# dual_encoder_i2c_revE.net
KiCad netlist of a schematic drawn in EAGLE
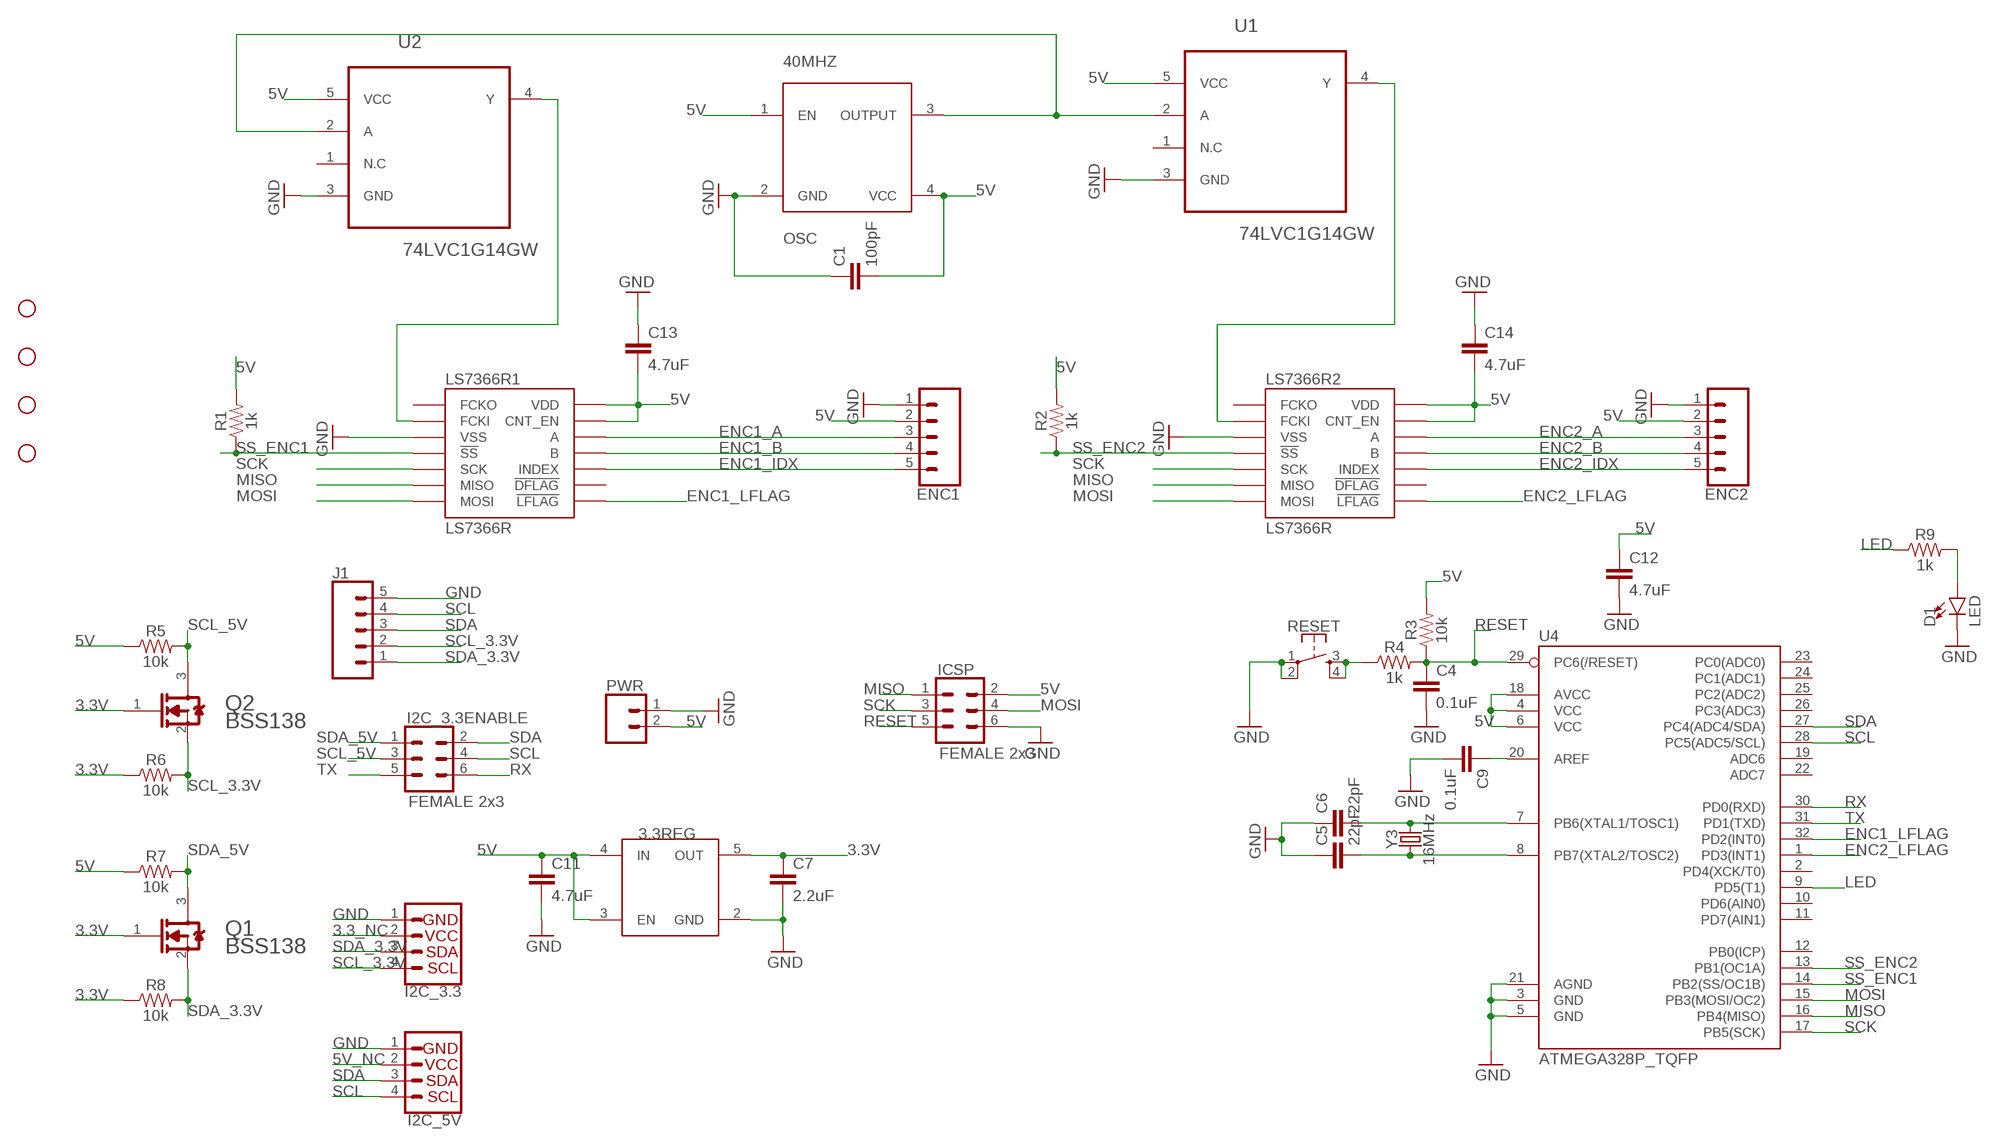
[diagram p0: schematic, sheet 1]

(export (version "E")
  (design (tool "Eeschema 10.0.6"))
  (components
    (comp (ref "3.3REG")
      (value "MIC3490-3.3YM5-TR")
      (footprint "eagle-import:SOT95P285X145-5N")
      (libsource (lib "eagle-import") (part "MIC3490-3.3YM5-TR"))
    )
    (comp (ref "40MHZ")
      (value "OSC")
      (footprint "eagle-import:CB3OSCILLATOR")
      (libsource (lib "eagle-import") (part "OSC"))
    )
    (comp (ref "C1")
      (value "100pF")
      (footprint "eagle-import:0603")
      (libsource (lib "eagle-import") (part "100PF-0603-50V-5%"))
    )
    (comp (ref "C4")
      (value "0.1uF")
      (footprint "eagle-import:0603")
      (libsource (lib "eagle-import") (part "0.1UF-0603-25V-5%"))
    )
    (comp (ref "C5")
      (value "22pF")
      (footprint "eagle-import:0603")
      (libsource (lib "eagle-import") (part "22PF-0603-50V-5%"))
    )
    (comp (ref "C6")
      (value "22pF")
      (footprint "eagle-import:0603")
      (libsource (lib "eagle-import") (part "22PF-0603-50V-5%"))
    )
    (comp (ref "C7")
      (value "2.2uF")
      (footprint "eagle-import:0603")
      (libsource (lib "eagle-import") (part "2.2UF-0603-10V-20%"))
    )
    (comp (ref "C9")
      (value "0.1uF")
      (footprint "eagle-import:0603")
      (libsource (lib "eagle-import") (part "0.1UF-0603-25V-5%"))
    )
    (comp (ref "C11")
      (value "4.7uF")
      (footprint "eagle-import:1206")
      (libsource (lib "eagle-import") (part "4.7UF-1206-16V-(+80/-20%)"))
    )
    (comp (ref "C12")
      (value "4.7uF")
      (footprint "eagle-import:1206")
      (libsource (lib "eagle-import") (part "4.7UF-1206-16V-(+80/-20%)"))
    )
    (comp (ref "C13")
      (value "4.7uF")
      (footprint "eagle-import:1206")
      (libsource (lib "eagle-import") (part "4.7UF-1206-16V-(+80/-20%)"))
    )
    (comp (ref "C14")
      (value "4.7uF")
      (footprint "eagle-import:1206")
      (libsource (lib "eagle-import") (part "4.7UF-1206-16V-(+80/-20%)"))
    )
    (comp (ref "D1")
      (value "LED")
      (footprint "eagle-import:LED-0603")
      (libsource (lib "eagle-import") (part "LED0603"))
    )
    (comp (ref "ENC1")
      (value "CONN_05")
      (footprint "eagle-import:1X05")
      (libsource (lib "eagle-import") (part "CONN_05"))
    )
    (comp (ref "ENC2")
      (value "CONN_05")
      (footprint "eagle-import:1X05")
      (libsource (lib "eagle-import") (part "CONN_05"))
    )
    (comp (ref "H1")
      (value "STAND-OFF")
      (footprint "eagle-import:STAND-OFF")
      (libsource (lib "eagle-import") (part "STAND-OFF"))
    )
    (comp (ref "H2")
      (value "STAND-OFF")
      (footprint "eagle-import:STAND-OFF")
      (libsource (lib "eagle-import") (part "STAND-OFF"))
    )
    (comp (ref "H3")
      (value "STAND-OFF")
      (footprint "eagle-import:STAND-OFF")
      (libsource (lib "eagle-import") (part "STAND-OFF"))
    )
    (comp (ref "H4")
      (value "STAND-OFF")
      (footprint "eagle-import:STAND-OFF")
      (libsource (lib "eagle-import") (part "STAND-OFF"))
    )
    (comp (ref "I2C_3.3")
      (value "QWIIC_CONNECTORJS-1MM")
      (footprint "eagle-import:JST04_1MM_RA")
      (libsource (lib "eagle-import") (part "QWIIC_CONNECTORJS-1MM"))
    )
    (comp (ref "I2C_3.3ENABLE")
      (value "FEMALE 2x3")
      (footprint "eagle-import:2X3")
      (libsource (lib "eagle-import") (part "CONN_03X2FEMALE"))
    )
    (comp (ref "I2C_5V")
      (value "QWIIC_CONNECTORJS-1MM")
      (footprint "eagle-import:JST04_1MM_RA")
      (libsource (lib "eagle-import") (part "QWIIC_CONNECTORJS-1MM"))
    )
    (comp (ref "ICSP")
      (value "FEMALE 2x3")
      (footprint "eagle-import:2X3")
      (libsource (lib "eagle-import") (part "CONN_03X2FEMALE"))
    )
    (comp (ref "J1")
      (value "CONN_05")
      (footprint "eagle-import:1X05")
      (libsource (lib "eagle-import") (part "CONN_05"))
    )
    (comp (ref "LS7366R1")
      (value "LS7366R")
      (footprint "eagle-import:SOIC14")
      (fields (field (name "MF") "LSI"))
      (libsource (lib "eagle-import") (part "LS7366R"))
    )
    (comp (ref "LS7366R2")
      (value "LS7366R")
      (footprint "eagle-import:SOIC14")
      (fields (field (name "MF") "LSI"))
      (libsource (lib "eagle-import") (part "LS7366R"))
    )
    (comp (ref "PWR")
      (value "CONN_02-JST-2MM-SMT")
      (footprint "eagle-import:JST-2-SMD")
      (libsource (lib "eagle-import") (part "CONN_02-JST-2MM-SMT"))
    )
    (comp (ref "Q1")
      (value "ON_SEMI_BSS138ON_SEMI_BSS138_0_0")
      (footprint "eagle-import:ON_SEMI_BSS138_0")
      (fields
        (field (name "DIGIKEY_PART_NUMBER") "BSS138CT-ND")
        (field (name "MF") "ON Semi")
        (field (name "MOUSER_PART_NUMBER") "512-BSS138")
      )
      (libsource (lib "eagle-import") (part "ON_SEMI_BSS138ON_SEMI_BSS138_0_0"))
    )
    (comp (ref "Q2")
      (value "ON_SEMI_BSS138ON_SEMI_BSS138_0_0")
      (footprint "eagle-import:ON_SEMI_BSS138_0")
      (fields
        (field (name "DIGIKEY_PART_NUMBER") "BSS138CT-ND")
        (field (name "MF") "ON Semi")
        (field (name "MOUSER_PART_NUMBER") "512-BSS138")
      )
      (libsource (lib "eagle-import") (part "ON_SEMI_BSS138ON_SEMI_BSS138_0_0"))
    )
    (comp (ref "R1")
      (value "1k")
      (footprint "eagle-import:0603")
      (libsource (lib "eagle-import") (part "1KOHM-0603-1/10W-1%"))
    )
    (comp (ref "R2")
      (value "1k")
      (footprint "eagle-import:0603")
      (libsource (lib "eagle-import") (part "1KOHM-0603-1/10W-1%"))
    )
    (comp (ref "R3")
      (value "10k")
      (footprint "eagle-import:0603")
      (libsource (lib "eagle-import") (part "10KOHM-0603-1/10W-1%"))
    )
    (comp (ref "R4")
      (value "1k")
      (footprint "eagle-import:0603")
      (libsource (lib "eagle-import") (part "1KOHM-0603-1/10W-1%"))
    )
    (comp (ref "R5")
      (value "10k")
      (footprint "eagle-import:0603")
      (libsource (lib "eagle-import") (part "10KOHM-0603-1/10W-1%"))
    )
    (comp (ref "R6")
      (value "10k")
      (footprint "eagle-import:0603")
      (libsource (lib "eagle-import") (part "10KOHM-0603-1/10W-1%"))
    )
    (comp (ref "R7")
      (value "10k")
      (footprint "eagle-import:0603")
      (libsource (lib "eagle-import") (part "10KOHM-0603-1/10W-1%"))
    )
    (comp (ref "R8")
      (value "10k")
      (footprint "eagle-import:0603")
      (libsource (lib "eagle-import") (part "10KOHM-0603-1/10W-1%"))
    )
    (comp (ref "R9")
      (value "1k")
      (footprint "eagle-import:0603")
      (libsource (lib "eagle-import") (part "1KOHM-0603-1/10W-1%"))
    )
    (comp (ref "RESET")
      (value "MOMENTARY-SWITCH-SPST-2-SMD-5.2MM")
      (footprint "eagle-import:TACTILE_SWITCH_SMD_5.2MM")
      (libsource (lib "eagle-import") (part "MOMENTARY-SWITCH-SPST-2-SMD-5.2MM"))
    )
    (comp (ref "U1")
      (value "74LVC1G14GW")
      (footprint "eagle-import:SOT65P210X110-5N")
      (fields (field (name "MF") "NXP Semiconductors"))
      (libsource (lib "eagle-import") (part "74LVC1G14GW"))
    )
    (comp (ref "U2")
      (value "74LVC1G14GW")
      (footprint "eagle-import:SOT65P210X110-5N")
      (fields (field (name "MF") "NXP Semiconductors"))
      (libsource (lib "eagle-import") (part "74LVC1G14GW"))
    )
    (comp (ref "U4")
      (value "ATMEGA328P_TQFP")
      (footprint "eagle-import:TQFP32-08")
      (libsource (lib "eagle-import") (part "ATMEGA328P_TQFP"))
    )
    (comp (ref "Y3")
      (value "16MHz")
      (footprint "eagle-import:CRYSTAL-SMD-5X3.2-4PAD")
      (libsource (lib "eagle-import") (part "CRYSTAL-16MHZSMD-5X3.2"))
    )
  )
  (nets
    (net (code "1") (name "/3.3V") (class "Default")
      (node (ref "3.3REG") (pin "5") (pinfunction "OUT_5") (pintype "output"))
      (node (ref "C7") (pin "1") (pinfunction "1_1") (pintype "passive"))
      (node (ref "Q1") (pin "1") (pinfunction "G_1") (pintype "bidirectional"))
      (node (ref "Q2") (pin "1") (pinfunction "G_1") (pintype "bidirectional"))
      (node (ref "R6") (pin "1") (pinfunction "1_1") (pintype "passive"))
      (node (ref "R8") (pin "1") (pinfunction "1_1") (pintype "passive"))
    )
    (net (code "2") (name "/3.3_NC") (class "Default")
      (node (ref "I2C_3.3") (pin "2") (pinfunction "2_2") (pintype "power_in"))
    )
    (net (code "3") (name "/5V") (class "Default")
      (node (ref "3.3REG") (pin "3") (pinfunction "EN_3") (pintype "input"))
      (node (ref "3.3REG") (pin "4") (pinfunction "IN_4") (pintype "input"))
      (node (ref "40MHZ") (pin "1") (pinfunction "EN_1") (pintype "input"))
      (node (ref "40MHZ") (pin "4") (pinfunction "VCC_4") (pintype "input"))
      (node (ref "C1") (pin "2") (pinfunction "2_2") (pintype "passive"))
      (node (ref "C11") (pin "1") (pinfunction "1_1") (pintype "passive"))
      (node (ref "C12") (pin "1") (pinfunction "1_1") (pintype "passive"))
      (node (ref "C13") (pin "2") (pinfunction "2_2") (pintype "passive"))
      (node (ref "C14") (pin "2") (pinfunction "2_2") (pintype "passive"))
      (node (ref "ENC1") (pin "2") (pinfunction "2_2") (pintype "passive"))
      (node (ref "ENC2") (pin "2") (pinfunction "2_2") (pintype "passive"))
      (node (ref "ICSP") (pin "2") (pinfunction "2_2") (pintype "bidirectional"))
      (node (ref "LS7366R1") (pin "13") (pinfunction "CNT_EN_13") (pintype "bidirectional"))
      (node (ref "LS7366R1") (pin "14") (pinfunction "VDD_14") (pintype "bidirectional"))
      (node (ref "LS7366R2") (pin "13") (pinfunction "CNT_EN_13") (pintype "bidirectional"))
      (node (ref "LS7366R2") (pin "14") (pinfunction "VDD_14") (pintype "bidirectional"))
      (node (ref "PWR") (pin "2") (pinfunction "1_2") (pintype "passive"))
      (node (ref "R1") (pin "2") (pinfunction "2_2") (pintype "passive"))
      (node (ref "R2") (pin "2") (pinfunction "2_2") (pintype "passive"))
      (node (ref "R3") (pin "2") (pinfunction "2_2") (pintype "passive"))
      (node (ref "R5") (pin "1") (pinfunction "1_1") (pintype "passive"))
      (node (ref "R7") (pin "1") (pinfunction "1_1") (pintype "passive"))
      (node (ref "U1") (pin "5") (pinfunction "VCC_5") (pintype "power_in"))
      (node (ref "U2") (pin "5") (pinfunction "VCC_5") (pintype "power_in"))
      (node (ref "U4") (pin "18") (pinfunction "AVCC_18") (pintype "bidirectional"))
      (node (ref "U4") (pin "4") (pinfunction "VCC_4") (pintype "bidirectional"))
      (node (ref "U4") (pin "6") (pinfunction "VCC_6") (pintype "bidirectional"))
    )
    (net (code "4") (name "/5V_NC") (class "Default")
      (node (ref "I2C_5V") (pin "2") (pinfunction "2_2") (pintype "power_in"))
    )
    (net (code "5") (name "/ENC1_A") (class "Default")
      (node (ref "ENC1") (pin "3") (pinfunction "3_3") (pintype "passive"))
      (node (ref "LS7366R1") (pin "12") (pinfunction "A_12") (pintype "bidirectional"))
    )
    (net (code "6") (name "/ENC1_B") (class "Default")
      (node (ref "ENC1") (pin "4") (pinfunction "4_4") (pintype "passive"))
      (node (ref "LS7366R1") (pin "11") (pinfunction "B_11") (pintype "bidirectional"))
    )
    (net (code "7") (name "/ENC1_IDX") (class "Default")
      (node (ref "ENC1") (pin "5") (pinfunction "5_5") (pintype "passive"))
      (node (ref "LS7366R1") (pin "10") (pinfunction "INDEX_10") (pintype "bidirectional"))
    )
    (net (code "8") (name "/ENC1_LFLAG") (class "Default")
      (node (ref "LS7366R1") (pin "8") (pinfunction "~{LFLAG}_8") (pintype "bidirectional"))
      (node (ref "U4") (pin "32") (pinfunction "PD2(INT0)_32") (pintype "bidirectional"))
    )
    (net (code "9") (name "/ENC2_A") (class "Default")
      (node (ref "ENC2") (pin "3") (pinfunction "3_3") (pintype "passive"))
      (node (ref "LS7366R2") (pin "12") (pinfunction "A_12") (pintype "bidirectional"))
    )
    (net (code "10") (name "/ENC2_B") (class "Default")
      (node (ref "ENC2") (pin "4") (pinfunction "4_4") (pintype "passive"))
      (node (ref "LS7366R2") (pin "11") (pinfunction "B_11") (pintype "bidirectional"))
    )
    (net (code "11") (name "/ENC2_IDX") (class "Default")
      (node (ref "ENC2") (pin "5") (pinfunction "5_5") (pintype "passive"))
      (node (ref "LS7366R2") (pin "10") (pinfunction "INDEX_10") (pintype "bidirectional"))
    )
    (net (code "12") (name "/ENC2_LFLAG") (class "Default")
      (node (ref "LS7366R2") (pin "8") (pinfunction "~{LFLAG}_8") (pintype "bidirectional"))
      (node (ref "U4") (pin "1") (pinfunction "PD3(INT1)_1") (pintype "bidirectional"))
    )
    (net (code "13") (name "/LED") (class "Default")
      (node (ref "R9") (pin "1") (pinfunction "1_1") (pintype "passive"))
      (node (ref "U4") (pin "9") (pinfunction "PD5(T1)_9") (pintype "bidirectional"))
    )
    (net (code "14") (name "/MISO") (class "Default")
      (node (ref "ICSP") (pin "1") (pinfunction "1_1") (pintype "bidirectional"))
      (node (ref "LS7366R1") (pin "6") (pinfunction "MISO_6") (pintype "bidirectional"))
      (node (ref "LS7366R2") (pin "6") (pinfunction "MISO_6") (pintype "bidirectional"))
      (node (ref "U4") (pin "16") (pinfunction "PB4(MISO)_16") (pintype "bidirectional"))
    )
    (net (code "15") (name "/MOSI") (class "Default")
      (node (ref "ICSP") (pin "4") (pinfunction "4_4") (pintype "bidirectional"))
      (node (ref "LS7366R1") (pin "7") (pinfunction "MOSI_7") (pintype "bidirectional"))
      (node (ref "LS7366R2") (pin "7") (pinfunction "MOSI_7") (pintype "bidirectional"))
      (node (ref "U4") (pin "15") (pinfunction "PB3(MOSI/OC2)_15") (pintype "bidirectional"))
    )
    (net (code "16") (name "/RESET") (class "Default")
      (node (ref "C4") (pin "1") (pinfunction "1_1") (pintype "passive"))
      (node (ref "ICSP") (pin "5") (pinfunction "5_5") (pintype "bidirectional"))
      (node (ref "R3") (pin "1") (pinfunction "1_1") (pintype "passive"))
      (node (ref "R4") (pin "2") (pinfunction "2_2") (pintype "passive"))
      (node (ref "U4") (pin "29") (pinfunction "PC6(/RESET)_29") (pintype "bidirectional"))
    )
    (net (code "17") (name "/RX") (class "Default")
      (node (ref "I2C_3.3ENABLE") (pin "6") (pinfunction "6_6") (pintype "bidirectional"))
      (node (ref "U4") (pin "30") (pinfunction "PD0(RXD)_30") (pintype "bidirectional"))
    )
    (net (code "18") (name "/SCK") (class "Default")
      (node (ref "ICSP") (pin "3") (pinfunction "3_3") (pintype "bidirectional"))
      (node (ref "LS7366R1") (pin "5") (pinfunction "SCK_5") (pintype "bidirectional"))
      (node (ref "LS7366R2") (pin "5") (pinfunction "SCK_5") (pintype "bidirectional"))
      (node (ref "U4") (pin "17") (pinfunction "PB5(SCK)_17") (pintype "bidirectional"))
    )
    (net (code "19") (name "/SCL") (class "Default")
      (node (ref "I2C_3.3ENABLE") (pin "4") (pinfunction "4_4") (pintype "bidirectional"))
      (node (ref "I2C_5V") (pin "4") (pinfunction "4_4") (pintype "passive"))
      (node (ref "J1") (pin "4") (pinfunction "4_4") (pintype "passive"))
      (node (ref "U4") (pin "28") (pinfunction "PC5(ADC5/SCL)_28") (pintype "bidirectional"))
    )
    (net (code "20") (name "/SCL_3.3V") (class "Default")
      (node (ref "I2C_3.3") (pin "4") (pinfunction "4_4") (pintype "passive"))
      (node (ref "J1") (pin "2") (pinfunction "2_2") (pintype "passive"))
      (node (ref "Q2") (pin "2") (pinfunction "S_2") (pintype "bidirectional"))
      (node (ref "R6") (pin "2") (pinfunction "2_2") (pintype "passive"))
    )
    (net (code "21") (name "/SCL_5V") (class "Default")
      (node (ref "I2C_3.3ENABLE") (pin "3") (pinfunction "3_3") (pintype "bidirectional"))
      (node (ref "Q2") (pin "3") (pinfunction "D_3") (pintype "bidirectional"))
      (node (ref "R5") (pin "2") (pinfunction "2_2") (pintype "passive"))
    )
    (net (code "22") (name "/SDA") (class "Default")
      (node (ref "I2C_3.3ENABLE") (pin "2") (pinfunction "2_2") (pintype "bidirectional"))
      (node (ref "I2C_5V") (pin "3") (pinfunction "3_3") (pintype "passive"))
      (node (ref "J1") (pin "3") (pinfunction "3_3") (pintype "passive"))
      (node (ref "U4") (pin "27") (pinfunction "PC4(ADC4/SDA)_27") (pintype "bidirectional"))
    )
    (net (code "23") (name "/SDA_3.3V") (class "Default")
      (node (ref "I2C_3.3") (pin "3") (pinfunction "3_3") (pintype "passive"))
      (node (ref "J1") (pin "1") (pinfunction "1_1") (pintype "passive"))
      (node (ref "Q1") (pin "2") (pinfunction "S_2") (pintype "bidirectional"))
      (node (ref "R8") (pin "2") (pinfunction "2_2") (pintype "passive"))
    )
    (net (code "24") (name "/SDA_5V") (class "Default")
      (node (ref "I2C_3.3ENABLE") (pin "1") (pinfunction "1_1") (pintype "bidirectional"))
      (node (ref "Q1") (pin "3") (pinfunction "D_3") (pintype "bidirectional"))
      (node (ref "R7") (pin "2") (pinfunction "2_2") (pintype "passive"))
    )
    (net (code "25") (name "/SS_ENC1") (class "Default")
      (node (ref "LS7366R1") (pin "4") (pinfunction "~{SS}_4") (pintype "bidirectional"))
      (node (ref "R1") (pin "1") (pinfunction "1_1") (pintype "passive"))
      (node (ref "U4") (pin "14") (pinfunction "PB2(SS/OC1B)_14") (pintype "bidirectional"))
    )
    (net (code "26") (name "/SS_ENC2") (class "Default")
      (node (ref "LS7366R2") (pin "4") (pinfunction "~{SS}_4") (pintype "bidirectional"))
      (node (ref "R2") (pin "1") (pinfunction "1_1") (pintype "passive"))
      (node (ref "U4") (pin "13") (pinfunction "PB1(OC1A)_13") (pintype "bidirectional"))
    )
    (net (code "27") (name "/TX") (class "Default")
      (node (ref "I2C_3.3ENABLE") (pin "5") (pinfunction "5_5") (pintype "bidirectional"))
      (node (ref "U4") (pin "31") (pinfunction "PD1(TXD)_31") (pintype "bidirectional"))
    )
    (net (code "28") (name "GND") (class "Default")
      (node (ref "3.3REG") (pin "2") (pinfunction "GND_2") (pintype "bidirectional"))
      (node (ref "40MHZ") (pin "2") (pinfunction "GND_2") (pintype "input"))
      (node (ref "C1") (pin "1") (pinfunction "1_1") (pintype "passive"))
      (node (ref "C11") (pin "2") (pinfunction "2_2") (pintype "passive"))
      (node (ref "C12") (pin "2") (pinfunction "2_2") (pintype "passive"))
      (node (ref "C13") (pin "1") (pinfunction "1_1") (pintype "passive"))
      (node (ref "C14") (pin "1") (pinfunction "1_1") (pintype "passive"))
      (node (ref "C4") (pin "2") (pinfunction "2_2") (pintype "passive"))
      (node (ref "C5") (pin "1") (pinfunction "1_1") (pintype "passive"))
      (node (ref "C6") (pin "1") (pinfunction "1_1") (pintype "passive"))
      (node (ref "C7") (pin "2") (pinfunction "2_2") (pintype "passive"))
      (node (ref "C9") (pin "2") (pinfunction "2_2") (pintype "passive"))
      (node (ref "D1") (pin "C") (pinfunction "C_C") (pintype "passive"))
      (node (ref "ENC1") (pin "1") (pinfunction "1_1") (pintype "passive"))
      (node (ref "ENC2") (pin "1") (pinfunction "1_1") (pintype "passive"))
      (node (ref "I2C_3.3") (pin "1") (pinfunction "1_1") (pintype "power_in"))
      (node (ref "I2C_5V") (pin "1") (pinfunction "1_1") (pintype "power_in"))
      (node (ref "ICSP") (pin "6") (pinfunction "6_6") (pintype "bidirectional"))
      (node (ref "J1") (pin "5") (pinfunction "5_5") (pintype "passive"))
      (node (ref "LS7366R1") (pin "3") (pinfunction "VSS_3") (pintype "bidirectional"))
      (node (ref "LS7366R2") (pin "3") (pinfunction "VSS_3") (pintype "bidirectional"))
      (node (ref "PWR") (pin "1") (pinfunction "2_1") (pintype "passive"))
      (node (ref "RESET") (pin "1") (pinfunction "1_1") (pintype "passive"))
      (node (ref "RESET") (pin "2") (pinfunction "2_2") (pintype "passive"))
      (node (ref "U1") (pin "3") (pinfunction "GND_3") (pintype "passive"))
      (node (ref "U2") (pin "3") (pinfunction "GND_3") (pintype "passive"))
      (node (ref "U4") (pin "21") (pinfunction "AGND_21") (pintype "bidirectional"))
      (node (ref "U4") (pin "3") (pinfunction "GND_3") (pintype "bidirectional"))
      (node (ref "U4") (pin "5") (pinfunction "GND_5") (pintype "bidirectional"))
    )
    (net (code "29") (name "Net-(40MHZ-OUTPUT)") (class "Default")
      (node (ref "40MHZ") (pin "3") (pinfunction "OUTPUT_3") (pintype "output"))
      (node (ref "U1") (pin "2") (pinfunction "A_2") (pintype "input"))
      (node (ref "U2") (pin "2") (pinfunction "A_2") (pintype "input"))
    )
    (net (code "30") (name "Net-(D1-PadA)") (class "Default")
      (node (ref "D1") (pin "A") (pinfunction "A_A") (pintype "passive"))
      (node (ref "R9") (pin "2") (pinfunction "2_2") (pintype "passive"))
    )
    (net (code "31") (name "Net-(LS7366R1-FCKI)") (class "Default")
      (node (ref "LS7366R1") (pin "2") (pinfunction "FCKI_2") (pintype "bidirectional"))
      (node (ref "U2") (pin "4") (pinfunction "Y_4") (pintype "output"))
    )
    (net (code "32") (name "Net-(LS7366R2-FCKI)") (class "Default")
      (node (ref "LS7366R2") (pin "2") (pinfunction "FCKI_2") (pintype "bidirectional"))
      (node (ref "U1") (pin "4") (pinfunction "Y_4") (pintype "output"))
    )
    (net (code "33") (name "Net-(R4-Pad1)") (class "Default")
      (node (ref "R4") (pin "1") (pinfunction "1_1") (pintype "passive"))
      (node (ref "RESET") (pin "3") (pinfunction "3_3") (pintype "passive"))
      (node (ref "RESET") (pin "4") (pinfunction "4_4") (pintype "passive"))
    )
    (net (code "34") (name "Net-(U4-AREF)") (class "Default")
      (node (ref "C9") (pin "1") (pinfunction "1_1") (pintype "passive"))
      (node (ref "U4") (pin "20") (pinfunction "AREF_20") (pintype "bidirectional"))
    )
    (net (code "35") (name "Net-(U4-PB6(XTAL1{slash}TOSC1))") (class "Default")
      (node (ref "C6") (pin "2") (pinfunction "2_2") (pintype "passive"))
      (node (ref "U4") (pin "7") (pinfunction "PB6(XTAL1/TOSC1)_7") (pintype "bidirectional"))
      (node (ref "Y3") (pin "3") (pinfunction "2_3") (pintype "passive"))
    )
    (net (code "36") (name "Net-(U4-PB7(XTAL2{slash}TOSC2))") (class "Default")
      (node (ref "C5") (pin "2") (pinfunction "2_2") (pintype "passive"))
      (node (ref "U4") (pin "8") (pinfunction "PB7(XTAL2/TOSC2)_8") (pintype "bidirectional"))
      (node (ref "Y3") (pin "1") (pinfunction "1_1") (pintype "passive"))
    )
    (net (code "37") (name "unconnected-(LS7366R1-FCKO-Pad1)") (class "Default")
      (node (ref "LS7366R1") (pin "1") (pinfunction "FCKO_1") (pintype "bidirectional"))
    )
    (net (code "38") (name "unconnected-(LS7366R1-~{DFLAG}-Pad9)") (class "Default")
      (node (ref "LS7366R1") (pin "9") (pinfunction "~{DFLAG}_9") (pintype "bidirectional"))
    )
    (net (code "39") (name "unconnected-(LS7366R2-FCKO-Pad1)") (class "Default")
      (node (ref "LS7366R2") (pin "1") (pinfunction "FCKO_1") (pintype "bidirectional"))
    )
    (net (code "40") (name "unconnected-(LS7366R2-~{DFLAG}-Pad9)") (class "Default")
      (node (ref "LS7366R2") (pin "9") (pinfunction "~{DFLAG}_9") (pintype "bidirectional"))
    )
    (net (code "41") (name "unconnected-(U1-N.C-Pad1)") (class "Default")
      (node (ref "U1") (pin "1") (pinfunction "N.C_1") (pintype "no_connect"))
    )
    (net (code "42") (name "unconnected-(U2-N.C-Pad1)") (class "Default")
      (node (ref "U2") (pin "1") (pinfunction "N.C_1") (pintype "no_connect"))
    )
    (net (code "43") (name "unconnected-(U4-ADC6-Pad19)") (class "Default")
      (node (ref "U4") (pin "19") (pinfunction "ADC6_19") (pintype "bidirectional"))
    )
    (net (code "44") (name "unconnected-(U4-ADC7-Pad22)") (class "Default")
      (node (ref "U4") (pin "22") (pinfunction "ADC7_22") (pintype "bidirectional"))
    )
    (net (code "45") (name "unconnected-(U4-PB0(ICP)-Pad12)") (class "Default")
      (node (ref "U4") (pin "12") (pinfunction "PB0(ICP)_12") (pintype "bidirectional"))
    )
    (net (code "46") (name "unconnected-(U4-PC0(ADC0)-Pad23)") (class "Default")
      (node (ref "U4") (pin "23") (pinfunction "PC0(ADC0)_23") (pintype "bidirectional"))
    )
    (net (code "47") (name "unconnected-(U4-PC1(ADC1)-Pad24)") (class "Default")
      (node (ref "U4") (pin "24") (pinfunction "PC1(ADC1)_24") (pintype "bidirectional"))
    )
    (net (code "48") (name "unconnected-(U4-PC2(ADC2)-Pad25)") (class "Default")
      (node (ref "U4") (pin "25") (pinfunction "PC2(ADC2)_25") (pintype "bidirectional"))
    )
    (net (code "49") (name "unconnected-(U4-PC3(ADC3)-Pad26)") (class "Default")
      (node (ref "U4") (pin "26") (pinfunction "PC3(ADC3)_26") (pintype "bidirectional"))
    )
    (net (code "50") (name "unconnected-(U4-PD4(XCK{slash}T0)-Pad2)") (class "Default")
      (node (ref "U4") (pin "2") (pinfunction "PD4(XCK/T0)_2") (pintype "bidirectional"))
    )
    (net (code "51") (name "unconnected-(U4-PD6(AIN0)-Pad10)") (class "Default")
      (node (ref "U4") (pin "10") (pinfunction "PD6(AIN0)_10") (pintype "bidirectional"))
    )
    (net (code "52") (name "unconnected-(U4-PD7(AIN1)-Pad11)") (class "Default")
      (node (ref "U4") (pin "11") (pinfunction "PD7(AIN1)_11") (pintype "bidirectional"))
    )
  )
)
